# Telemetry_MCU.net
KiCad netlist of a schematic drawn in Altium Designer
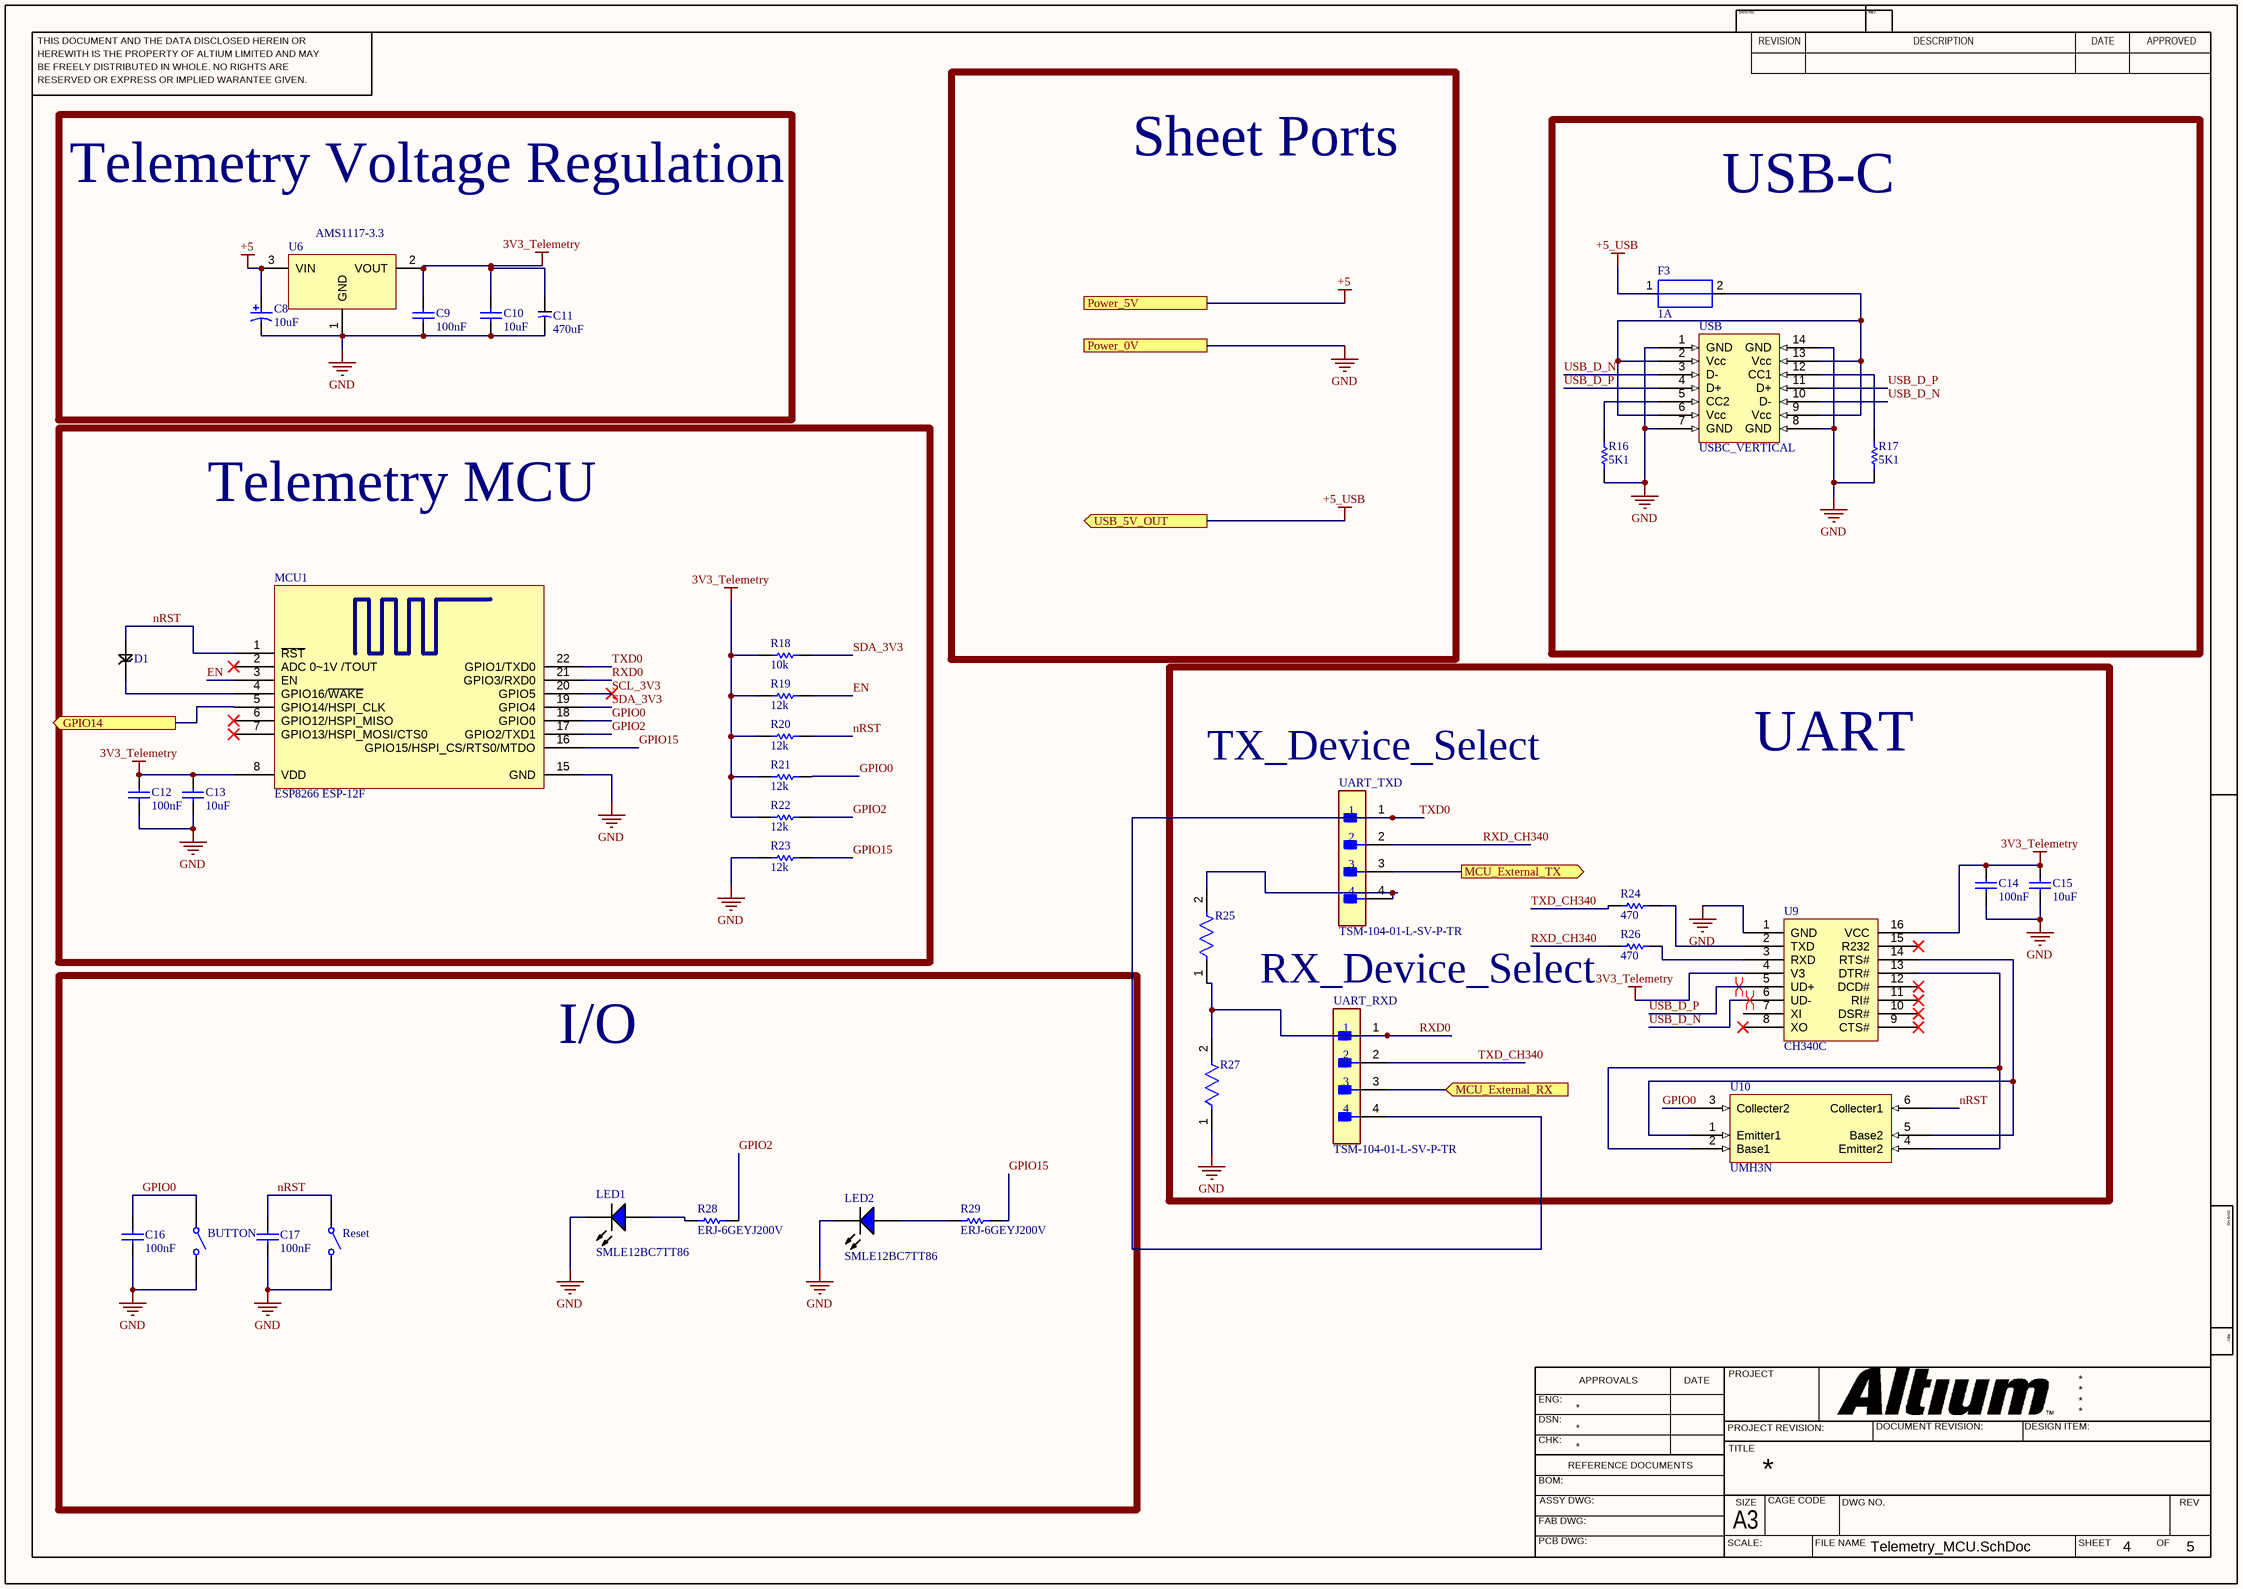
[diagram p0: Telemetry_MCU.SchDoc]

(export (version "E")
  (design (tool "Eeschema 10.0.6"))
  (components
    (comp (ref "BUTTON")
      (value "434111050826")
      (footprint "434111050826")
      (description "WS-TASV SMD Tact Switch 6.0X3.5 mm")
      (fields (field (name "MANUFACTURER") "Wuerth Elektronik"))
      (libsource (lib "Altium Content Vault") (part "WE-TACT-SW-2"))
    )
    (comp (ref "C8")
      (value "10uF")
      (footprint "KEMT-A-3216-18-2_M")
      (description "Capacitor, Tantalum, 10 uF, +/- 10%, 10 V, -55 to 125 degC, 2-Pin SMD (1206), RoHS, Tape and Reel")
      (fields (field (name "TOLERANCE") "±10%") (field (name "MANUFACTURER") "Kemet"))
      (libsource (lib "Altium Content Vault") (part "CAP-P-2"))
    )
    (comp (ref "C9")
      (value "100nF")
      (footprint "CAPC2013X88X50NL20T25")
      (fields (field (name "PART NUMBER") "C0805C104K5RACTU") (field (name "MANUFACTURER") "Kemet"))
      (libsource (lib "Altium Content Vault") (part "CAP"))
    )
    (comp (ref "C10")
      (value "10uF")
      (footprint "CAPC2013X140X50NL20T25")
      (fields (field (name "PART NUMBER") "C0805C106K8PACTU") (field (name "MANUFACTURER") "Kemet"))
      (libsource (lib "Altium Content Vault") (part "CAP"))
    )
    (comp (ref "C11")
      (value "470uF")
      (footprint "ULR477M1AE85RR")
      (libsource (lib "Schlib1") (part "ULR477M1AE85RR"))
    )
    (comp (ref "C12")
      (value "100nF")
      (footprint "CAPC2013X88X50NL20T25")
      (fields (field (name "PART NUMBER") "C0805C104K5RACTU") (field (name "MANUFACTURER") "Kemet"))
      (libsource (lib "Altium Content Vault") (part "CAP"))
    )
    (comp (ref "C13")
      (value "10uF")
      (footprint "CAPC2013X140X50NL20T25")
      (fields (field (name "PART NUMBER") "C0805C106K8PACTU") (field (name "MANUFACTURER") "Kemet"))
      (libsource (lib "Altium Content Vault") (part "CAP"))
    )
    (comp (ref "C14")
      (value "100nF")
      (footprint "CAPC2013X88X50NL20T25")
      (fields (field (name "PART NUMBER") "C0805C104K5RACTU") (field (name "MANUFACTURER") "Kemet"))
      (libsource (lib "Altium Content Vault") (part "CAP"))
    )
    (comp (ref "C15")
      (value "10uF")
      (footprint "CAPC2013X140X50NL20T25")
      (fields (field (name "PART NUMBER") "C0805C106K8PACTU") (field (name "MANUFACTURER") "Kemet"))
      (libsource (lib "Altium Content Vault") (part "CAP"))
    )
    (comp (ref "C16")
      (value "100nF")
      (footprint "CAPC2013X88X50NL20T25")
      (fields (field (name "PART NUMBER") "C0805C104K5RACTU") (field (name "MANUFACTURER") "Kemet"))
      (libsource (lib "Altium Content Vault") (part "CAP"))
    )
    (comp (ref "C17")
      (value "100nF")
      (footprint "CAPC2013X88X50NL20T25")
      (fields (field (name "PART NUMBER") "C0805C104K5RACTU") (field (name "MANUFACTURER") "Kemet"))
      (libsource (lib "Altium Content Vault") (part "CAP"))
    )
    (comp (ref "D1")
      (value "DFLS230L-7")
      (footprint "DFLS230L-7")
      (libsource (lib "Schlib1") (part "DFLS230L-7"))
    )
    (comp (ref "F3")
      (value "1A")
      (footprint "0ZCG0050AF2C")
      (description "PTC Resettable Fuse 0.5A(hold) 1A(trip) 30VDC 100A 0.8W 0.15s 0.15Ohm SMD Solder Pad 1812 T/R")
      (fields (field (name "MANUFACTURER") "Bel") (field (name "MANUFACTURER PART NUMBER") "0ZCG0050AF2C"))
      (libsource (lib "HB_Driver") (part "0ZCG0050AF2C"))
    )
    (comp (ref "LED1")
      (value "SMLE12BC7TT86")
      (footprint "ROHM-SMLE12BC7TT86_V")
      (description "Blue LED, 2.9 V, 20 mA, -30 to 85 degC, 2-Pin SMD, RoHS, Tape and Reel")
      (fields (field (name "MANUFACTURER") "Rohm"))
      (libsource (lib "Altium Content Vault") (part "LED-BLUE-AK-2"))
    )
    (comp (ref "LED2")
      (value "SMLE12BC7TT86")
      (footprint "ROHM-SMLE12BC7TT86_V")
      (description "Blue LED, 2.9 V, 20 mA, -30 to 85 degC, 2-Pin SMD, RoHS, Tape and Reel")
      (fields (field (name "MANUFACTURER") "Rohm"))
      (libsource (lib "Altium Content Vault") (part "LED-BLUE-AK-2"))
    )
    (comp (ref "MCU1")
      (value "ESP8266 ESP-12F")
      (footprint "ESP8266 ESP_12F - Danon NoSPI")
      (libsource (lib "Schlib1") (part "ESP8266 ESP-12F - Danon - NoSPI"))
    )
    (comp (ref "R16")
      (value "5K1")
      (footprint "RESC2013X50X30NL20T20")
      (fields (field (name "MANUFACTURER") "Vishay Dale") (field (name "PART NUMBER") "CRCW08055K10FKEA"))
      (libsource (lib "Altium Content Vault") (part "RES"))
    )
    (comp (ref "R17")
      (value "5K1")
      (footprint "RESC2013X50X30NL20T20")
      (fields (field (name "MANUFACTURER") "Vishay Dale") (field (name "PART NUMBER") "CRCW08055K10FKEA"))
      (libsource (lib "Altium Content Vault") (part "RES"))
    )
    (comp (ref "R18")
      (value "10k")
      (footprint "RESC2013X60X40NL20T25_A")
      (fields (field (name "TOLERANCE") "0.1%") (field (name "MANUFACTURER") "Panasonic"))
      (libsource (lib "Altium Content Vault") (part "RES-2"))
    )
    (comp (ref "R19")
      (value "12k")
      (footprint "RESC2013X60X40NL20T25_A")
      (fields (field (name "TOLERANCE") "0.1%") (field (name "MANUFACTURER") "Panasonic"))
      (libsource (lib "Altium Content Vault") (part "RES-2"))
    )
    (comp (ref "R20")
      (value "12k")
      (footprint "RESC2013X60X40NL20T25_A")
      (fields (field (name "TOLERANCE") "0.1%") (field (name "MANUFACTURER") "Panasonic"))
      (libsource (lib "Altium Content Vault") (part "RES-2"))
    )
    (comp (ref "R21")
      (value "12k")
      (footprint "RESC2013X60X40NL20T25_A")
      (fields (field (name "TOLERANCE") "0.1%") (field (name "MANUFACTURER") "Panasonic"))
      (libsource (lib "Altium Content Vault") (part "RES-2"))
    )
    (comp (ref "R22")
      (value "12k")
      (footprint "RESC2013X60X40NL20T25_A")
      (fields (field (name "TOLERANCE") "0.1%") (field (name "MANUFACTURER") "Panasonic"))
      (libsource (lib "Altium Content Vault") (part "RES-2"))
    )
    (comp (ref "R23")
      (value "12k")
      (footprint "RESC2013X60X40NL20T25_A")
      (fields (field (name "TOLERANCE") "0.1%") (field (name "MANUFACTURER") "Panasonic"))
      (libsource (lib "Altium Content Vault") (part "RES-2"))
    )
    (comp (ref "R24")
      (value "470")
      (footprint "RESC2013X50X30NL20T20")
      (fields (field (name "MANUFACTURER") "Vishay Dale") (field (name "PART NUMBER") "CRCW0805470KFKEA"))
      (libsource (lib "Altium Content Vault") (part "RES"))
    )
    (comp (ref "R25")
      (value "CRCW080510K0FKEA")
      (footprint "FP-CRCW0805-e3-IPC_A")
      (description "RES Thick Film, 10kΩ, 1%, 0.125W, 100ppm/°C, 0805")
      (fields (field (name "TOLERANCE") "1%"))
      (libsource (lib "Altium Content Vault") (part "1029c3af85768c4190bb7ad29bc67b5"))
    )
    (comp (ref "R26")
      (value "470")
      (footprint "RESC2013X50X30NL20T20")
      (fields (field (name "MANUFACTURER") "Vishay Dale") (field (name "PART NUMBER") "CRCW0805470KFKEA"))
      (libsource (lib "Altium Content Vault") (part "RES"))
    )
    (comp (ref "R27")
      (value "CRCW080510K0FKEA")
      (footprint "FP-CRCW0805-e3-IPC_A")
      (description "RES Thick Film, 10kΩ, 1%, 0.125W, 100ppm/°C, 0805")
      (fields (field (name "TOLERANCE") "1%"))
      (libsource (lib "Altium Content Vault") (part "1029c3af85768c4190bb7ad29bc67b5"))
    )
    (comp (ref "R28")
      (value "ERJ-6GEYJ200V")
      (footprint "RESC2013X70X40LL20T20")
      (fields (field (name "MANUFACTURER") "Panasonic"))
      (libsource (lib "Altium Content Vault") (part "RES"))
    )
    (comp (ref "R29")
      (value "ERJ-6GEYJ200V")
      (footprint "RESC2013X70X40LL20T20")
      (fields (field (name "MANUFACTURER") "Panasonic"))
      (libsource (lib "Altium Content Vault") (part "RES"))
    )
    (comp (ref "Reset")
      (value "434111050826")
      (footprint "434111050826")
      (description "WS-TASV SMD Tact Switch 6.0X3.5 mm")
      (fields (field (name "MANUFACTURER") "Wuerth Elektronik"))
      (libsource (lib "Altium Content Vault") (part "WE-TACT-SW-2"))
    )
    (comp (ref "U6")
      (value "AMS1117-3.3")
      (footprint "SOT-223")
      (description "3.3V  3-Terminal Adjustable Positive Voltage Regulator")
      (libsource (lib "Schlib1") (part "AMS1117-3.3"))
    )
    (comp (ref "U9")
      (value "CH340C")
      (footprint "SOP16_50Mil_PinPitch")
      (libsource (lib "Schlib1") (part "CH340C"))
    )
    (comp (ref "U10") (value "UMH3N") (footprint "UMH3N") (libsource (lib "Schlib1") (part "UMH3N")))
    (comp (ref "UART_RXD")
      (value "TSM-104-01-L-SV-P-TR")
      (footprint "FP-TSM-104-01-L-SV-P-TR-MFG")
      (description "CONN HEADER SMD 4POS 2.54MM")
      (fields
        (field (name "MANUFACTURER") "Samtec")
        (field (name "OCTOPART") "https://octopart.com/tsm-104-01-l-sv-p-tr-samtec-6805355")
      )
      (libsource (lib "Altium Content Vault") (part "299a8cea1bdcbc3624fe62c390fa72c"))
    )
    (comp (ref "UART_TXD")
      (value "TSM-104-01-L-SV-P-TR")
      (footprint "FP-TSM-104-01-L-SV-P-TR-MFG")
      (description "CONN HEADER SMD 4POS 2.54MM")
      (fields
        (field (name "MANUFACTURER") "Samtec")
        (field (name "OCTOPART") "https://octopart.com/tsm-104-01-l-sv-p-tr-samtec-6805355")
      )
      (libsource (lib "Altium Content Vault") (part "299a8cea1bdcbc3624fe62c390fa72c"))
    )
    (comp (ref "USB")
      (value "USBC_VERTICAL")
      (footprint "USBC_Vertical")
      (libsource (lib "Schlib1") (part "USBC_VERTICAL"))
    )
  )
  (nets
    (net (code "1") (name "+5") (class "Default")
      (node (ref "C8") (pin "1") (pinfunction "1_1") (pintype "passive"))
      (node (ref "U6") (pin "3") (pinfunction "VIN_3") (pintype "passive"))
    )
    (net (code "2") (name "+5_USB") (class "Default")
      (node (ref "F3") (pin "1") (pinfunction "+_1") (pintype "passive"))
    )
    (net (code "3") (name "/EN") (class "Default")
      (node (ref "MCU1") (pin "3") (pinfunction "EN_3") (pintype "passive"))
      (node (ref "R19") (pin "2") (pinfunction "2_2") (pintype "passive"))
    )
    (net (code "4") (name "/GPIO0") (class "Default")
      (node (ref "BUTTON") (pin "1") (pinfunction "1_1") (pintype "passive"))
      (node (ref "C16") (pin "2") (pinfunction "2_2") (pintype "passive"))
      (node (ref "MCU1") (pin "18") (pinfunction "GPIO0_18") (pintype "passive"))
      (node (ref "R21") (pin "2") (pinfunction "2_2") (pintype "passive"))
      (node (ref "U10") (pin "3") (pinfunction "Collecter2_3") (pintype "input"))
    )
    (net (code "5") (name "/GPIO2") (class "Default")
      (node (ref "MCU1") (pin "17") (pinfunction "GPIO2/TXD1_17") (pintype "passive"))
      (node (ref "R22") (pin "2") (pinfunction "2_2") (pintype "passive"))
      (node (ref "R28") (pin "2") (pinfunction "2_2") (pintype "passive"))
    )
    (net (code "6") (name "/GPIO14") (class "Default")
      (node (ref "MCU1") (pin "5") (pinfunction "GPIO14/HSPI_CLK_5") (pintype "passive"))
    )
    (net (code "7") (name "/GPIO15") (class "Default")
      (node (ref "MCU1") (pin "16") (pinfunction "GPIO15/HSPI_CS/RTS0/MTDO_16") (pintype "passive"))
      (node (ref "R23") (pin "2") (pinfunction "2_2") (pintype "passive"))
      (node (ref "R29") (pin "2") (pinfunction "2_2") (pintype "passive"))
    )
    (net (code "8") (name "/MCU_External_RX") (class "Default")
      (node (ref "UART_RXD") (pin "3") (pinfunction "3_3") (pintype "passive"))
    )
    (net (code "9") (name "/MCU_External_TX") (class "Default")
      (node (ref "UART_TXD") (pin "3") (pinfunction "3_3") (pintype "passive"))
    )
    (net (code "10") (name "/RXD0") (class "Default")
      (node (ref "MCU1") (pin "21") (pinfunction "GPIO3/RXD0_21") (pintype "passive"))
      (node (ref "R25") (pin "1") (pinfunction "1_1") (pintype "passive"))
      (node (ref "R27") (pin "2") (pinfunction "2_2") (pintype "passive"))
      (node (ref "UART_RXD") (pin "1") (pinfunction "1_1") (pintype "passive"))
    )
    (net (code "11") (name "/RXD_CH340") (class "Default")
      (node (ref "R26") (pin "1") (pinfunction "1_1") (pintype "passive"))
      (node (ref "UART_TXD") (pin "2") (pinfunction "2_2") (pintype "passive"))
    )
    (net (code "12") (name "/SCL_3V3") (class "Default")
      (node (ref "MCU1") (pin "20") (pinfunction "GPIO5_20") (pintype "passive+no_connect"))
    )
    (net (code "13") (name "/SDA_3V3") (class "Default")
      (node (ref "MCU1") (pin "19") (pinfunction "GPIO4_19") (pintype "passive"))
      (node (ref "R18") (pin "2") (pinfunction "2_2") (pintype "passive"))
    )
    (net (code "14") (name "/TXD0") (class "Default")
      (node (ref "MCU1") (pin "22") (pinfunction "GPIO1/TXD0_22") (pintype "passive"))
      (node (ref "UART_RXD") (pin "4") (pinfunction "4_4") (pintype "passive"))
      (node (ref "UART_TXD") (pin "1") (pinfunction "1_1") (pintype "passive"))
    )
    (net (code "15") (name "/TXD_CH340") (class "Default")
      (node (ref "R24") (pin "1") (pinfunction "1_1") (pintype "passive"))
      (node (ref "UART_RXD") (pin "2") (pinfunction "2_2") (pintype "passive"))
    )
    (net (code "16") (name "/USB_D_N") (class "Default")
      (node (ref "U9") (pin "6") (pinfunction "UD-_6") (pintype "passive"))
      (node (ref "USB") (pin "10") (pinfunction "D-_10") (pintype "input"))
      (node (ref "USB") (pin "3") (pinfunction "D-_3") (pintype "input"))
    )
    (net (code "17") (name "/USB_D_P") (class "Default")
      (node (ref "U9") (pin "5") (pinfunction "UD+_5") (pintype "passive"))
      (node (ref "USB") (pin "11") (pinfunction "D+_11") (pintype "input"))
      (node (ref "USB") (pin "4") (pinfunction "D+_4") (pintype "input"))
    )
    (net (code "18") (name "/nRST") (class "Default")
      (node (ref "C17") (pin "2") (pinfunction "2_2") (pintype "passive"))
      (node (ref "D1") (pin "1") (pinfunction "3_1") (pintype "passive"))
      (node (ref "MCU1") (pin "1") (pinfunction "~{RST}_1") (pintype "passive"))
      (node (ref "R20") (pin "2") (pinfunction "2_2") (pintype "passive"))
      (node (ref "Reset") (pin "1") (pinfunction "1_1") (pintype "passive"))
      (node (ref "U10") (pin "6") (pinfunction "Collecter1_6") (pintype "input"))
    )
    (net (code "19") (name "3V3_Telemetry") (class "Default")
      (node (ref "C10") (pin "2") (pinfunction "2_2") (pintype "passive"))
      (node (ref "C11") (pin "2") (pinfunction "5_2") (pintype "passive"))
      (node (ref "C12") (pin "2") (pinfunction "2_2") (pintype "passive"))
      (node (ref "C13") (pin "2") (pinfunction "2_2") (pintype "passive"))
      (node (ref "C14") (pin "2") (pinfunction "2_2") (pintype "passive"))
      (node (ref "C15") (pin "2") (pinfunction "2_2") (pintype "passive"))
      (node (ref "C9") (pin "2") (pinfunction "2_2") (pintype "passive"))
      (node (ref "MCU1") (pin "8") (pinfunction "VDD_8") (pintype "passive"))
      (node (ref "R18") (pin "1") (pinfunction "1_1") (pintype "passive"))
      (node (ref "R19") (pin "1") (pinfunction "1_1") (pintype "passive"))
      (node (ref "R20") (pin "1") (pinfunction "1_1") (pintype "passive"))
      (node (ref "R21") (pin "1") (pinfunction "1_1") (pintype "passive"))
      (node (ref "R22") (pin "1") (pinfunction "1_1") (pintype "passive"))
      (node (ref "U6") (pin "2") (pinfunction "VOUT_2") (pintype "passive"))
      (node (ref "U9") (pin "16") (pinfunction "VCC_16") (pintype "passive"))
      (node (ref "U9") (pin "4") (pinfunction "V3_4") (pintype "passive"))
    )
    (net (code "20") (name "GND") (class "Default")
      (node (ref "BUTTON") (pin "2") (pinfunction "2_2") (pintype "passive"))
      (node (ref "C10") (pin "1") (pinfunction "1_1") (pintype "passive"))
      (node (ref "C11") (pin "1") (pinfunction "4_1") (pintype "passive"))
      (node (ref "C12") (pin "1") (pinfunction "1_1") (pintype "passive"))
      (node (ref "C13") (pin "1") (pinfunction "1_1") (pintype "passive"))
      (node (ref "C14") (pin "1") (pinfunction "1_1") (pintype "passive"))
      (node (ref "C15") (pin "1") (pinfunction "1_1") (pintype "passive"))
      (node (ref "C16") (pin "1") (pinfunction "1_1") (pintype "passive"))
      (node (ref "C17") (pin "1") (pinfunction "1_1") (pintype "passive"))
      (node (ref "C8") (pin "2") (pinfunction "2_2") (pintype "passive"))
      (node (ref "C9") (pin "1") (pinfunction "1_1") (pintype "passive"))
      (node (ref "LED1") (pin "2") (pinfunction "K_2") (pintype "passive"))
      (node (ref "LED2") (pin "2") (pinfunction "K_2") (pintype "passive"))
      (node (ref "MCU1") (pin "15") (pinfunction "GND_15") (pintype "passive"))
      (node (ref "R16") (pin "1") (pinfunction "1_1") (pintype "passive"))
      (node (ref "R17") (pin "1") (pinfunction "1_1") (pintype "passive"))
      (node (ref "R23") (pin "1") (pinfunction "1_1") (pintype "passive"))
      (node (ref "R27") (pin "1") (pinfunction "1_1") (pintype "passive"))
      (node (ref "Reset") (pin "2") (pinfunction "2_2") (pintype "passive"))
      (node (ref "U6") (pin "1") (pinfunction "GND_1") (pintype "passive"))
      (node (ref "U9") (pin "1") (pinfunction "GND_1") (pintype "passive"))
      (node (ref "USB") (pin "1") (pinfunction "GND_1") (pintype "input"))
      (node (ref "USB") (pin "14") (pinfunction "GND_14") (pintype "input"))
      (node (ref "USB") (pin "7") (pinfunction "GND_7") (pintype "input"))
      (node (ref "USB") (pin "8") (pinfunction "GND_8") (pintype "input"))
    )
    (net (code "21") (name "Net-(F3--)") (class "Default")
      (node (ref "F3") (pin "2") (pinfunction "-_2") (pintype "passive"))
      (node (ref "USB") (pin "13") (pinfunction "Vcc_13") (pintype "input"))
      (node (ref "USB") (pin "2") (pinfunction "Vcc_2") (pintype "input"))
      (node (ref "USB") (pin "6") (pinfunction "Vcc_6") (pintype "input"))
      (node (ref "USB") (pin "9") (pinfunction "Vcc_9") (pintype "input"))
    )
    (net (code "22") (name "Net-(LED1-A)") (class "Default")
      (node (ref "LED1") (pin "1") (pinfunction "A_1") (pintype "passive"))
      (node (ref "R28") (pin "1") (pinfunction "1_1") (pintype "passive"))
    )
    (net (code "23") (name "Net-(LED2-A)") (class "Default")
      (node (ref "LED2") (pin "1") (pinfunction "A_1") (pintype "passive"))
      (node (ref "R29") (pin "1") (pinfunction "1_1") (pintype "passive"))
    )
    (net (code "24") (name "Net-(MCU1-GPIO16{slash}~{WAKE})") (class "Default")
      (node (ref "D1") (pin "2") (pinfunction "2_2") (pintype "passive"))
      (node (ref "MCU1") (pin "4") (pinfunction "GPIO16/~{WAKE}_4") (pintype "passive"))
    )
    (net (code "25") (name "Net-(R25-Pad2)") (class "Default")
      (node (ref "R25") (pin "2") (pinfunction "2_2") (pintype "passive"))
      (node (ref "UART_TXD") (pin "4") (pinfunction "4_4") (pintype "passive"))
    )
    (net (code "26") (name "Net-(U9-RXD)") (class "Default")
      (node (ref "R26") (pin "2") (pinfunction "2_2") (pintype "passive"))
      (node (ref "U9") (pin "3") (pinfunction "RXD_3") (pintype "passive"))
    )
    (net (code "27") (name "Net-(U9-TXD)") (class "Default")
      (node (ref "R24") (pin "2") (pinfunction "2_2") (pintype "passive"))
      (node (ref "U9") (pin "2") (pinfunction "TXD_2") (pintype "passive"))
    )
    (net (code "28") (name "Net-(U10-Base1)") (class "Default")
      (node (ref "U10") (pin "2") (pinfunction "Base1_2") (pintype "input"))
      (node (ref "U10") (pin "4") (pinfunction "Emitter2_4") (pintype "input"))
      (node (ref "U9") (pin "13") (pinfunction "DTR#_13") (pintype "passive"))
    )
    (net (code "29") (name "Net-(U10-Base2)") (class "Default")
      (node (ref "U10") (pin "1") (pinfunction "Emitter1_1") (pintype "input"))
      (node (ref "U10") (pin "5") (pinfunction "Base2_5") (pintype "input"))
      (node (ref "U9") (pin "14") (pinfunction "RTS#_14") (pintype "passive"))
    )
    (net (code "30") (name "Net-(USB-CC1)") (class "Default")
      (node (ref "R17") (pin "2") (pinfunction "2_2") (pintype "passive"))
      (node (ref "USB") (pin "12") (pinfunction "CC1_12") (pintype "input"))
    )
    (net (code "31") (name "Net-(USB-CC2)") (class "Default")
      (node (ref "R16") (pin "2") (pinfunction "2_2") (pintype "passive"))
      (node (ref "USB") (pin "5") (pinfunction "CC2_5") (pintype "input"))
    )
    (net (code "32") (name "unconnected-(MCU1-ADC_0~1V_{slash}TOUT-Pad2)") (class "Default")
      (node (ref "MCU1") (pin "2") (pinfunction "ADC_0~1V_/TOUT_2") (pintype "passive+no_connect"))
    )
    (net (code "33") (name "unconnected-(MCU1-GPIO12{slash}HSPI_MISO-Pad6)") (class "Default")
      (node (ref "MCU1") (pin "6") (pinfunction "GPIO12/HSPI_MISO_6") (pintype "passive+no_connect"))
    )
    (net (code "34") (name "unconnected-(MCU1-GPIO13{slash}HSPI_MOSI{slash}CTS0-Pad7)") (class "Default")
      (node (ref "MCU1") (pin "7") (pinfunction "GPIO13/HSPI_MOSI/CTS0_7") (pintype "passive+no_connect"))
    )
    (net (code "35") (name "unconnected-(U9-CTS#-Pad9)") (class "Default")
      (node (ref "U9") (pin "9") (pinfunction "CTS#_9") (pintype "passive+no_connect"))
    )
    (net (code "36") (name "unconnected-(U9-DCD#-Pad12)") (class "Default")
      (node (ref "U9") (pin "12") (pinfunction "DCD#_12") (pintype "passive+no_connect"))
    )
    (net (code "37") (name "unconnected-(U9-DSR#-Pad10)") (class "Default")
      (node (ref "U9") (pin "10") (pinfunction "DSR#_10") (pintype "passive+no_connect"))
    )
    (net (code "38") (name "unconnected-(U9-R232-Pad15)") (class "Default")
      (node (ref "U9") (pin "15") (pinfunction "R232_15") (pintype "passive+no_connect"))
    )
    (net (code "39") (name "unconnected-(U9-RI#-Pad11)") (class "Default")
      (node (ref "U9") (pin "11") (pinfunction "RI#_11") (pintype "passive+no_connect"))
    )
    (net (code "40") (name "unconnected-(U9-XI-Pad7)") (class "Default")
      (node (ref "U9") (pin "7") (pinfunction "XI_7") (pintype "passive"))
    )
    (net (code "41") (name "unconnected-(U9-XO-Pad8)") (class "Default")
      (node (ref "U9") (pin "8") (pinfunction "XO_8") (pintype "passive+no_connect"))
    )
  )
)
